# balancingBridge.net
KiCad netlist of a schematic drawn in Altium Designer
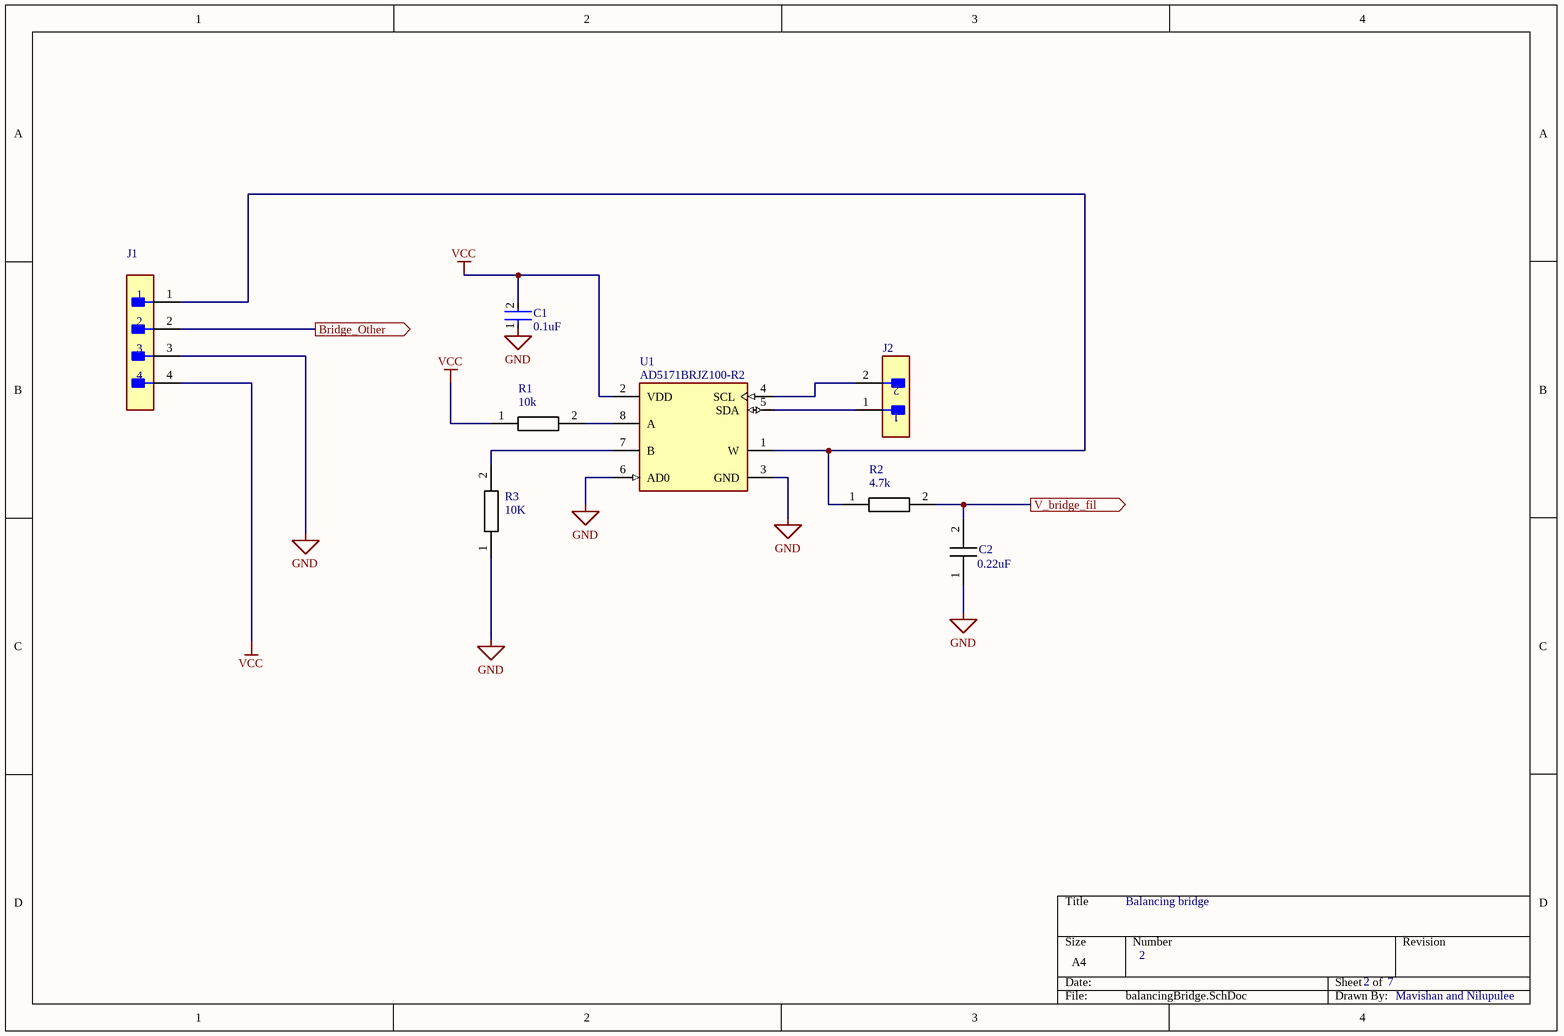
[diagram p0: balancingBridge.SchDoc]

(export (version "E")
  (design (tool "Eeschema 10.0.6"))
  (components
    (comp (ref "C1")
      (value "0.1uF")
      (footprint "FP-C1206C-EB-MFG")
      (description "CAP CER 0.1UF 25V C0G/NP0 1206")
      (fields
        (field (name "MANUFACTURER") "KEMET")
        (field (name "MANUFACTURER PART NUMBER") "C1206C104F3GACTU")
      )
      (libsource (lib "Altium Content Vault") (part "b4654b650e69147ec39a6b967a45e02"))
    )
    (comp (ref "C2")
      (value "12063C224JAT2A")
      (footprint "SamacSys:CAPC3216X94N")
      (description "Capacitor")
      (fields (field (name "MOUSER PART NUMBER") "581-12063C224JAT2A") (field (name "PARAMETER 1") "0.22uF"))
      (libsource (lib "SamacSys") (part "12063C224JAT2A"))
    )
    (comp (ref "J1")
      (value "B4B-XH-A(LF)(SN)")
      (footprint "FP-B4B-XH-A_LF_SN-MFG")
      (description "CONN HEADER VERT 4POS 2.5MM")
      (libsource (lib "Altium Content Vault") (part "299a8cea1bdcbc3624fe62c390fa72c"))
    )
    (comp (ref "J2")
      (value "M20-9990246")
      (footprint "FP-M20-9990246-MFG")
      (description "CONN HEADER VERT 2POS 2.54MM")
      (fields
        (field (name "OCTOPART") "https://octopart.com/m20-9990246-harwin-2590635")
        (field (name "MANUFACTURER") "Harwin")
      )
      (libsource (lib "Altium Content Vault") (part "3bc925449376181038e59eaffc5286c"))
    )
    (comp (ref "R1")
      (value "ERA-8AEB103V")
      (footprint "SamacSys:RESC3216X70N")
      (description "Resistor")
      (fields (field (name "MOUSER PART NUMBER") "667-ERA-8AEB103V") (field (name "PARAMETER 1") "10k"))
      (libsource (lib "SamacSys") (part "ERA-8AEB103V"))
    )
    (comp (ref "R2")
      (value "CHP1206AFX-4701ELF")
      (footprint "SamacSys:RESC3116X65N")
      (description "Resistor")
      (fields (field (name "MOUSER PART NUMBER") "652-CHP1206AFX-4701L") (field (name "PARAMETER 1") "4.7k"))
      (libsource (lib "*") (part "CHP1206AFX-4701ELF"))
    )
    (comp (ref "R3")
      (value "ERA-8AEB103V")
      (footprint "SamacSys:RESC3216X70N")
      (description "Resistor")
      (fields (field (name "MOUSER PART NUMBER") "667-ERA-8AEB103V") (field (name "PARAMETER 1") "10K"))
      (libsource (lib "SamacSys") (part "ERA-8AEB103V"))
    )
    (comp (ref "U1")
      (value "AD5171BRJZ100-R2")
      (footprint "FP-RJ-8-IPC_A")
      (description "AD5171BRJZ100-R2 Digital Potentiometer 64POS 100kOhm Single Automotive 8-Pin SOT-23 T/R")
      (fields (field (name "TOLERANCE") "30%"))
      (libsource (lib "Altium Content Vault") (part "b7c56c75a673f54426577c74fe16793"))
    )
  )
  (nets
    (net (code "1") (name "/Bridge_Other") (class "Default")
      (node (ref "J1") (pin "2") (pinfunction "2_2") (pintype "passive"))
    )
    (net (code "2") (name "/V_bridge_fil") (class "Default")
      (node (ref "C2") (pin "2") (pinfunction "C2_2") (pintype "passive"))
      (node (ref "R2") (pin "2") (pinfunction "2_2") (pintype "passive"))
    )
    (net (code "3") (name "GND") (class "Default")
      (node (ref "C1") (pin "1") (pinfunction "1_1") (pintype "passive"))
      (node (ref "C2") (pin "1") (pinfunction "C1_1") (pintype "passive"))
      (node (ref "J1") (pin "3") (pinfunction "3_3") (pintype "passive"))
      (node (ref "R3") (pin "1") (pinfunction "1_1") (pintype "passive"))
      (node (ref "U1") (pin "3") (pinfunction "GND_3") (pintype "power_in"))
      (node (ref "U1") (pin "6") (pinfunction "AD0_6") (pintype "input"))
    )
    (net (code "4") (name "Net-(U1-A)") (class "Default")
      (node (ref "R1") (pin "2") (pinfunction "2_2") (pintype "passive"))
      (node (ref "U1") (pin "8") (pinfunction "A_8") (pintype "passive"))
    )
    (net (code "5") (name "Net-(U1-B)") (class "Default")
      (node (ref "R3") (pin "2") (pinfunction "2_2") (pintype "passive"))
      (node (ref "U1") (pin "7") (pinfunction "B_7") (pintype "passive"))
    )
    (net (code "6") (name "Net-(U1-SCL)") (class "Default")
      (node (ref "J2") (pin "2") (pinfunction "2_2") (pintype "passive"))
      (node (ref "U1") (pin "4") (pinfunction "SCL_4") (pintype "input"))
    )
    (net (code "7") (name "Net-(U1-SDA)") (class "Default")
      (node (ref "J2") (pin "1") (pinfunction "1_1") (pintype "passive"))
      (node (ref "U1") (pin "5") (pinfunction "SDA_5") (pintype "bidirectional"))
    )
    (net (code "8") (name "Net-(U1-W)") (class "Default")
      (node (ref "J1") (pin "1") (pinfunction "1_1") (pintype "passive"))
      (node (ref "R2") (pin "1") (pinfunction "1_1") (pintype "passive"))
      (node (ref "U1") (pin "1") (pinfunction "W_1") (pintype "passive"))
    )
    (net (code "9") (name "VCC") (class "Default")
      (node (ref "C1") (pin "2") (pinfunction "2_2") (pintype "passive"))
      (node (ref "J1") (pin "4") (pinfunction "4_4") (pintype "passive"))
      (node (ref "R1") (pin "1") (pinfunction "1_1") (pintype "passive"))
      (node (ref "U1") (pin "2") (pinfunction "VDD_2") (pintype "power_in"))
    )
  )
)
